# Avery_Bellis_Schematic.net
KiCad netlist of a schematic drawn in EAGLE
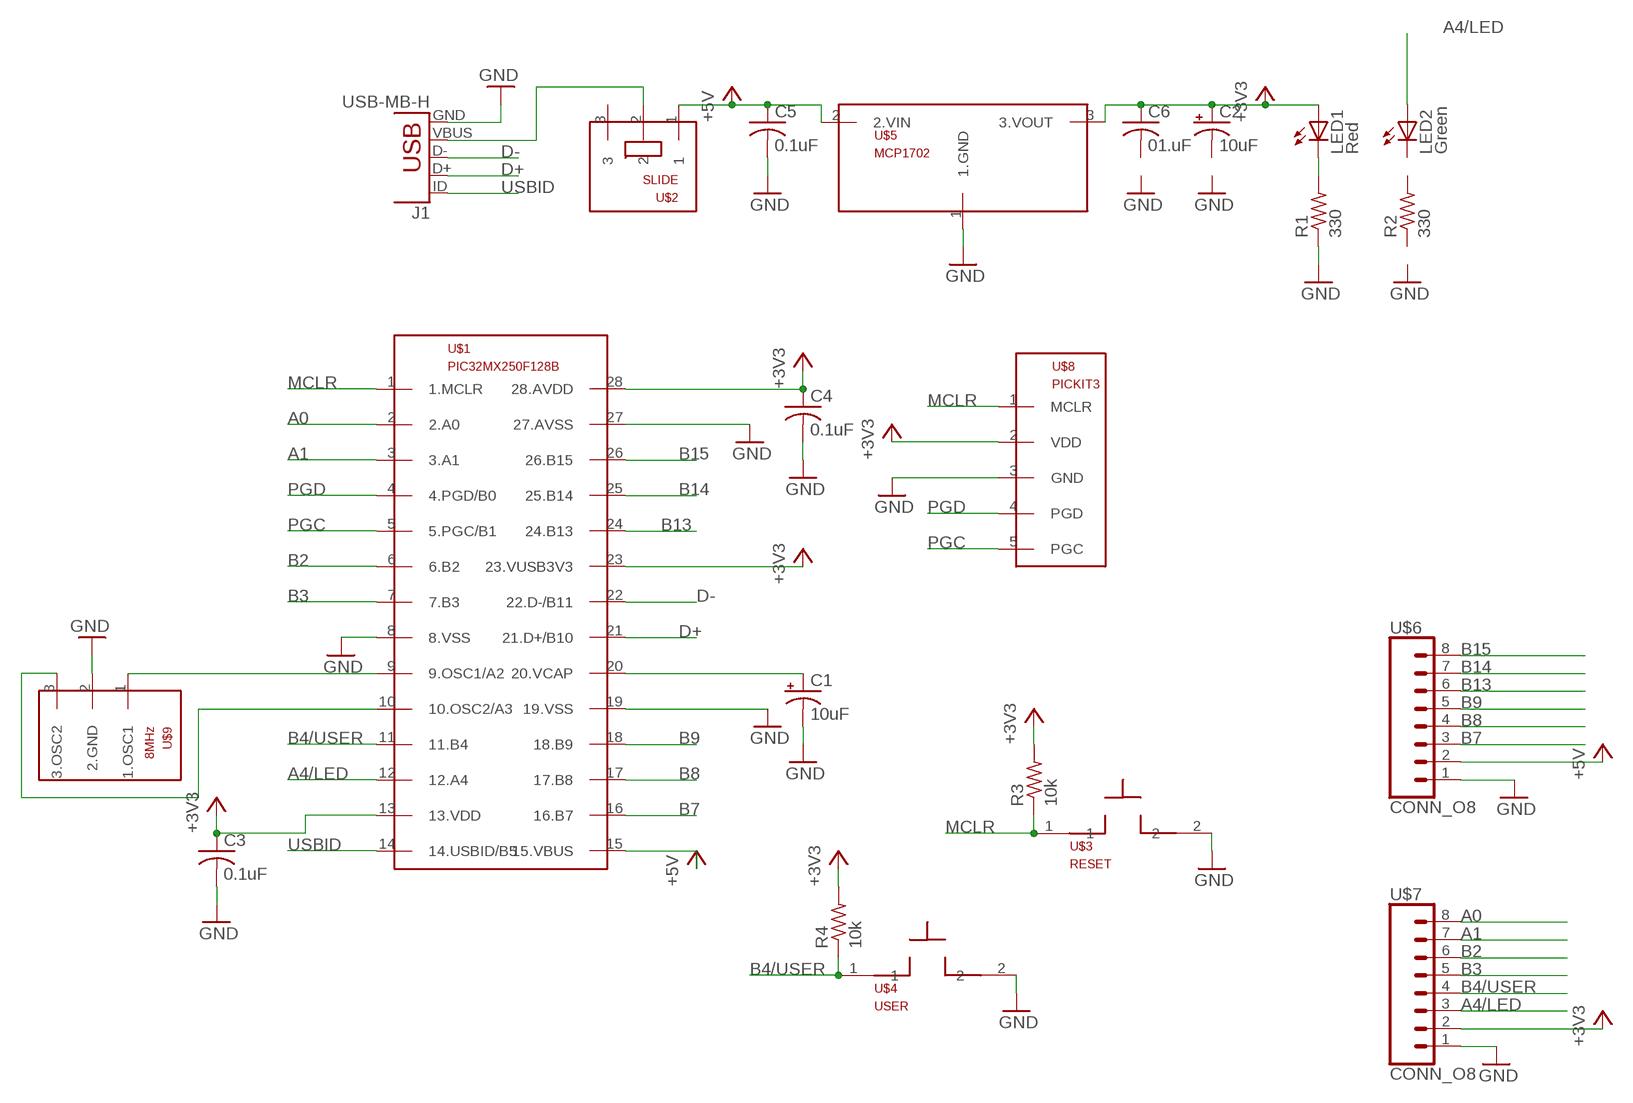
[diagram p0: schematic, sheet 1]

(export (version "E")
  (design (tool "Eeschema 10.0.6"))
  (components
    (comp (ref "C1")
      (value "10uF")
      (footprint "eagle-import:B45181B")
      (libsource (lib "eagle-import") (part "CPOL-USB45181B"))
    )
    (comp (ref "C2")
      (value "10uF")
      (footprint "eagle-import:B45181B")
      (libsource (lib "eagle-import") (part "CPOL-USB45181B"))
    )
    (comp (ref "C3")
      (value "0.1uF")
      (footprint "eagle-import:C025-025X050")
      (libsource (lib "eagle-import") (part "C-US025-025X050"))
    )
    (comp (ref "C4")
      (value "0.1uF")
      (footprint "eagle-import:C025-025X050")
      (libsource (lib "eagle-import") (part "C-US025-025X050"))
    )
    (comp (ref "C5")
      (value "0.1uF")
      (footprint "eagle-import:C025-025X050")
      (libsource (lib "eagle-import") (part "C-US025-025X050"))
    )
    (comp (ref "C6")
      (value "01.uF")
      (footprint "eagle-import:C025-025X050")
      (libsource (lib "eagle-import") (part "C-US025-025X050"))
    )
    (comp (ref "J1")
      (value "USB-MB-H")
      (footprint "eagle-import:USB-MB-H")
      (libsource (lib "eagle-import") (part "USB-MB-H"))
    )
    (comp (ref "LED1")
      (value "Red")
      (footprint "eagle-import:LED3MM")
      (libsource (lib "eagle-import") (part "LED3MM"))
    )
    (comp (ref "LED2")
      (value "Green")
      (footprint "eagle-import:LED3MM")
      (libsource (lib "eagle-import") (part "LED3MM"))
    )
    (comp (ref "R1")
      (value "330")
      (footprint "eagle-import:0207_10")
      (libsource (lib "eagle-import") (part "R-US_0207/10"))
    )
    (comp (ref "R2")
      (value "330")
      (footprint "eagle-import:0207_10")
      (libsource (lib "eagle-import") (part "R-US_0207/10"))
    )
    (comp (ref "R3")
      (value "10k")
      (footprint "eagle-import:0207_10")
      (libsource (lib "eagle-import") (part "R-US_0207/10"))
    )
    (comp (ref "R4")
      (value "10k")
      (footprint "eagle-import:0207_10")
      (libsource (lib "eagle-import") (part "R-US_0207/10"))
    )
    (comp (ref "U$1")
      (value "PIC32MX250F128B")
      (footprint "eagle-import:DIL28-3")
      (libsource (lib "eagle-import") (part "PIC32MX250F128B"))
    )
    (comp (ref "U$2")
      (value "SLIDE")
      (footprint "eagle-import:SLIDE")
      (libsource (lib "eagle-import") (part "SLIDE"))
    )
    (comp (ref "U$3")
      (value "RESET")
      (footprint "eagle-import:PUSHB")
      (libsource (lib "eagle-import") (part "PUSHB"))
    )
    (comp (ref "U$4")
      (value "USER")
      (footprint "eagle-import:PUSHB")
      (libsource (lib "eagle-import") (part "PUSHB"))
    )
    (comp (ref "U$5")
      (value "MCP1702")
      (footprint "eagle-import:TO92")
      (libsource (lib "eagle-import") (part "MCP1702"))
    )
    (comp (ref "U$6")
      (value "CONN_O8")
      (footprint "eagle-import:1X08")
      (libsource (lib "eagle-import") (part "CONN_O8"))
    )
    (comp (ref "U$7")
      (value "CONN_O8")
      (footprint "eagle-import:1X08")
      (libsource (lib "eagle-import") (part "CONN_O8"))
    )
    (comp (ref "U$8")
      (value "PICKIT3")
      (footprint "eagle-import:1X05")
      (libsource (lib "eagle-import") (part "PICKIT3"))
    )
    (comp (ref "U$9")
      (value "8MHz")
      (footprint "eagle-import:OSC")
      (libsource (lib "eagle-import") (part "OSC"))
    )
  )
  (nets
    (net (code "1") (name "+3V3") (class "Default")
      (node (ref "C2") (pin "+") (pinfunction "+_+") (pintype "passive"))
      (node (ref "C3") (pin "1") (pinfunction "1_1") (pintype "passive"))
      (node (ref "C4") (pin "1") (pinfunction "1_1") (pintype "passive"))
      (node (ref "C6") (pin "1") (pinfunction "1_1") (pintype "passive"))
      (node (ref "LED1") (pin "A") (pinfunction "A_A") (pintype "passive"))
      (node (ref "R3") (pin "2") (pinfunction "2_2") (pintype "passive"))
      (node (ref "R4") (pin "2") (pinfunction "2_2") (pintype "passive"))
      (node (ref "U$1") (pin "13") (pinfunction "13.VDD_13") (pintype "bidirectional"))
      (node (ref "U$1") (pin "23") (pinfunction "23.VUSB3V3_23") (pintype "bidirectional"))
      (node (ref "U$1") (pin "28") (pinfunction "28.AVDD_28") (pintype "bidirectional"))
      (node (ref "U$5") (pin "3") (pinfunction "3.VOUT_3") (pintype "bidirectional"))
      (node (ref "U$7") (pin "2") (pinfunction "2_2") (pintype "passive"))
      (node (ref "U$8") (pin "2") (pinfunction "VDD_2") (pintype "bidirectional"))
    )
    (net (code "2") (name "+5V") (class "Default")
      (node (ref "C5") (pin "1") (pinfunction "1_1") (pintype "passive"))
      (node (ref "U$1") (pin "15") (pinfunction "15.VBUS_15") (pintype "bidirectional"))
      (node (ref "U$2") (pin "1") (pinfunction "1_1") (pintype "bidirectional"))
      (node (ref "U$5") (pin "2") (pinfunction "2.VIN_2") (pintype "bidirectional"))
      (node (ref "U$6") (pin "2") (pinfunction "2_2") (pintype "passive"))
    )
    (net (code "3") (name "/A0") (class "Default")
      (node (ref "U$1") (pin "2") (pinfunction "2.A0_2") (pintype "bidirectional"))
      (node (ref "U$7") (pin "8") (pinfunction "8_8") (pintype "passive"))
    )
    (net (code "4") (name "/A1") (class "Default")
      (node (ref "U$1") (pin "3") (pinfunction "3.A1_3") (pintype "bidirectional"))
      (node (ref "U$7") (pin "7") (pinfunction "7_7") (pintype "passive"))
    )
    (net (code "5") (name "/A4{slash}LED") (class "Default")
      (node (ref "LED2") (pin "A") (pinfunction "A_A") (pintype "passive"))
      (node (ref "U$1") (pin "12") (pinfunction "12.A4_12") (pintype "bidirectional"))
      (node (ref "U$7") (pin "3") (pinfunction "3_3") (pintype "passive"))
    )
    (net (code "6") (name "/B2") (class "Default")
      (node (ref "U$1") (pin "6") (pinfunction "6.B2_6") (pintype "bidirectional"))
      (node (ref "U$7") (pin "6") (pinfunction "6_6") (pintype "passive"))
    )
    (net (code "7") (name "/B3") (class "Default")
      (node (ref "U$1") (pin "7") (pinfunction "7.B3_7") (pintype "bidirectional"))
      (node (ref "U$7") (pin "5") (pinfunction "5_5") (pintype "passive"))
    )
    (net (code "8") (name "/B4{slash}USER") (class "Default")
      (node (ref "R4") (pin "1") (pinfunction "1_1") (pintype "passive"))
      (node (ref "U$1") (pin "11") (pinfunction "11.B4_11") (pintype "bidirectional"))
      (node (ref "U$4") (pin "1") (pinfunction "1_1") (pintype "bidirectional"))
      (node (ref "U$7") (pin "4") (pinfunction "4_4") (pintype "passive"))
    )
    (net (code "9") (name "/B7") (class "Default")
      (node (ref "U$1") (pin "16") (pinfunction "16.B7_16") (pintype "bidirectional"))
      (node (ref "U$6") (pin "3") (pinfunction "3_3") (pintype "passive"))
    )
    (net (code "10") (name "/B8") (class "Default")
      (node (ref "U$1") (pin "17") (pinfunction "17.B8_17") (pintype "bidirectional"))
      (node (ref "U$6") (pin "4") (pinfunction "4_4") (pintype "passive"))
    )
    (net (code "11") (name "/B9") (class "Default")
      (node (ref "U$1") (pin "18") (pinfunction "18.B9_18") (pintype "bidirectional"))
      (node (ref "U$6") (pin "5") (pinfunction "5_5") (pintype "passive"))
    )
    (net (code "12") (name "/B13") (class "Default")
      (node (ref "U$1") (pin "24") (pinfunction "24.B13_24") (pintype "bidirectional"))
      (node (ref "U$6") (pin "6") (pinfunction "6_6") (pintype "passive"))
    )
    (net (code "13") (name "/B14") (class "Default")
      (node (ref "U$1") (pin "25") (pinfunction "25.B14_25") (pintype "bidirectional"))
      (node (ref "U$6") (pin "7") (pinfunction "7_7") (pintype "passive"))
    )
    (net (code "14") (name "/B15") (class "Default")
      (node (ref "U$1") (pin "26") (pinfunction "26.B15_26") (pintype "bidirectional"))
      (node (ref "U$6") (pin "8") (pinfunction "8_8") (pintype "passive"))
    )
    (net (code "15") (name "/D+") (class "Default")
      (node (ref "J1") (pin "D+") (pinfunction "D+_D+") (pintype "bidirectional"))
      (node (ref "U$1") (pin "21") (pinfunction "21.D+/B10_21") (pintype "bidirectional"))
    )
    (net (code "16") (name "/D-") (class "Default")
      (node (ref "J1") (pin "D-") (pinfunction "D-_D-") (pintype "bidirectional"))
      (node (ref "U$1") (pin "22") (pinfunction "22.D-/B11_22") (pintype "bidirectional"))
    )
    (net (code "17") (name "/MCLR") (class "Default")
      (node (ref "R3") (pin "1") (pinfunction "1_1") (pintype "passive"))
      (node (ref "U$1") (pin "1") (pinfunction "1.MCLR_1") (pintype "bidirectional"))
      (node (ref "U$3") (pin "1") (pinfunction "1_1") (pintype "bidirectional"))
      (node (ref "U$8") (pin "1") (pinfunction "MCLR_1") (pintype "bidirectional"))
    )
    (net (code "18") (name "/PGC") (class "Default")
      (node (ref "U$1") (pin "5") (pinfunction "5.PGC/B1_5") (pintype "bidirectional"))
      (node (ref "U$8") (pin "5") (pinfunction "PGC_5") (pintype "bidirectional"))
    )
    (net (code "19") (name "/PGD") (class "Default")
      (node (ref "U$1") (pin "4") (pinfunction "4.PGD/B0_4") (pintype "bidirectional"))
      (node (ref "U$8") (pin "4") (pinfunction "PGD_4") (pintype "bidirectional"))
    )
    (net (code "20") (name "/USBID") (class "Default")
      (node (ref "J1") (pin "ID") (pinfunction "ID_ID") (pintype "bidirectional"))
      (node (ref "U$1") (pin "14") (pinfunction "14.USBID/B5_14") (pintype "bidirectional"))
    )
    (net (code "21") (name "GND") (class "Default")
      (node (ref "C1") (pin "-") (pinfunction "-_-") (pintype "passive"))
      (node (ref "C3") (pin "2") (pinfunction "2_2") (pintype "passive"))
      (node (ref "C4") (pin "2") (pinfunction "2_2") (pintype "passive"))
      (node (ref "C5") (pin "2") (pinfunction "2_2") (pintype "passive"))
      (node (ref "J1") (pin "GND") (pinfunction "GND_GND") (pintype "bidirectional"))
      (node (ref "R1") (pin "1") (pinfunction "1_1") (pintype "passive"))
      (node (ref "U$1") (pin "19") (pinfunction "19.VSS_19") (pintype "bidirectional"))
      (node (ref "U$1") (pin "27") (pinfunction "27.AVSS_27") (pintype "bidirectional"))
      (node (ref "U$1") (pin "8") (pinfunction "8.VSS_8") (pintype "bidirectional"))
      (node (ref "U$3") (pin "2") (pinfunction "2_2") (pintype "bidirectional"))
      (node (ref "U$4") (pin "2") (pinfunction "2_2") (pintype "bidirectional"))
      (node (ref "U$5") (pin "1") (pinfunction "1.GND_1") (pintype "bidirectional"))
      (node (ref "U$6") (pin "1") (pinfunction "1_1") (pintype "passive"))
      (node (ref "U$7") (pin "1") (pinfunction "1_1") (pintype "passive"))
      (node (ref "U$8") (pin "3") (pinfunction "GND_3") (pintype "bidirectional"))
      (node (ref "U$9") (pin "2") (pinfunction "2.GND_2") (pintype "bidirectional"))
    )
    (net (code "22") (name "Net-(J1-PadVBUS)") (class "Default")
      (node (ref "J1") (pin "VBUS") (pinfunction "VBUS_VBUS") (pintype "bidirectional"))
      (node (ref "U$2") (pin "2") (pinfunction "2_2") (pintype "bidirectional"))
    )
    (net (code "23") (name "Net-(LED1-C)") (class "Default")
      (node (ref "LED1") (pin "K") (pinfunction "C_K") (pintype "passive"))
      (node (ref "R1") (pin "2") (pinfunction "2_2") (pintype "passive"))
    )
    (net (code "24") (name "Net-(U$1-9.OSC1{slash}A2)") (class "Default")
      (node (ref "U$1") (pin "9") (pinfunction "9.OSC1/A2_9") (pintype "bidirectional"))
      (node (ref "U$9") (pin "1") (pinfunction "1.OSC1_1") (pintype "bidirectional"))
    )
    (net (code "25") (name "Net-(U$1-10.OSC2{slash}A3)") (class "Default")
      (node (ref "U$1") (pin "10") (pinfunction "10.OSC2/A3_10") (pintype "bidirectional"))
      (node (ref "U$9") (pin "3") (pinfunction "3.OSC2_3") (pintype "bidirectional"))
    )
    (net (code "26") (name "Net-(U$1-20.VCAP)") (class "Default")
      (node (ref "C1") (pin "+") (pinfunction "+_+") (pintype "passive"))
      (node (ref "U$1") (pin "20") (pinfunction "20.VCAP_20") (pintype "bidirectional"))
    )
    (net (code "27") (name "unconnected-(C2-Pad-)") (class "Default")
      (node (ref "C2") (pin "-") (pinfunction "-_-") (pintype "passive"))
    )
    (net (code "28") (name "unconnected-(C6-Pad2)") (class "Default")
      (node (ref "C6") (pin "2") (pinfunction "2_2") (pintype "passive"))
    )
    (net (code "29") (name "unconnected-(LED2-C-PadK)") (class "Default")
      (node (ref "LED2") (pin "K") (pinfunction "C_K") (pintype "passive"))
    )
    (net (code "30") (name "unconnected-(R2-Pad1)") (class "Default")
      (node (ref "R2") (pin "1") (pinfunction "1_1") (pintype "passive"))
    )
    (net (code "31") (name "unconnected-(R2-Pad2)") (class "Default")
      (node (ref "R2") (pin "2") (pinfunction "2_2") (pintype "passive"))
    )
    (net (code "32") (name "unconnected-(U$2-Pad3)") (class "Default")
      (node (ref "U$2") (pin "3") (pinfunction "3_3") (pintype "bidirectional"))
    )
  )
)
